# design.net
KiCad netlist of a schematic drawn in Altium Designer
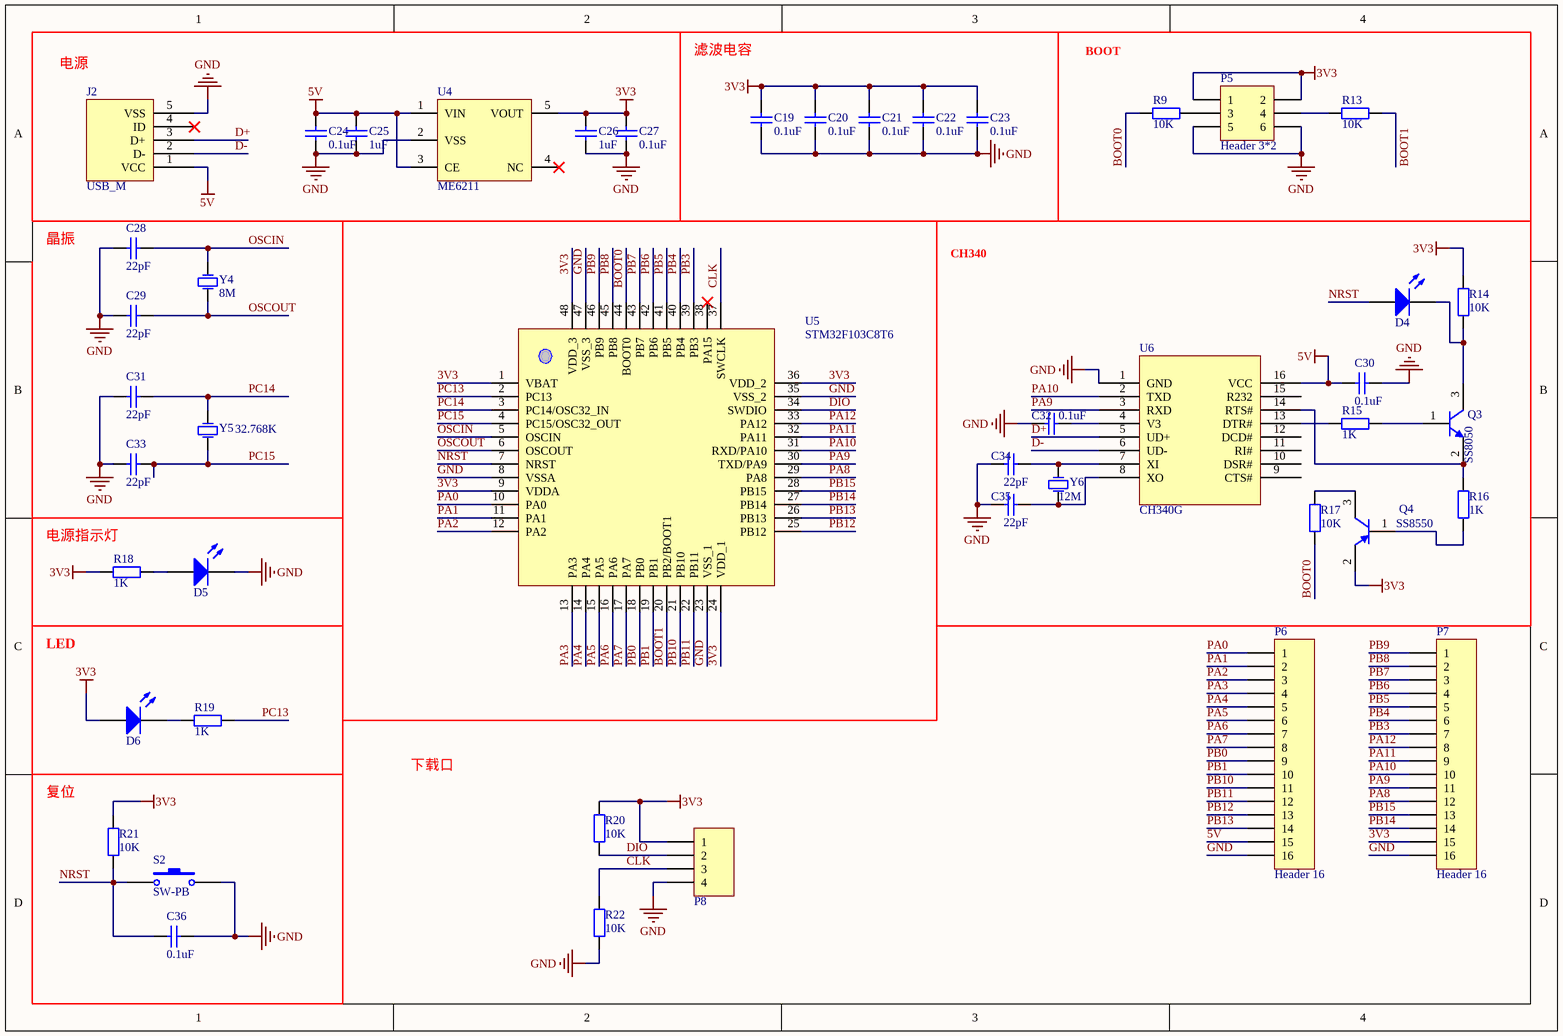
[diagram p0: 原理图.SchDoc]

(export (version "E")
  (design (tool "Eeschema 10.0.6"))
  (components
    (comp (ref "C19")
      (value "0.1uF")
      (footprint "0603_C")
      (description "无极性电容")
      (fields (field (name "Comment") "Cap") (field (name "PUBLISHER") "Altium Limited"))
      (libsource (lib "stm32test") (part "Cap"))
    )
    (comp (ref "C20")
      (value "0.1uF")
      (footprint "0603_C")
      (description "无极性电容")
      (fields (field (name "Comment") "Cap") (field (name "PUBLISHER") "Altium Limited"))
      (libsource (lib "stm32test") (part "Cap"))
    )
    (comp (ref "C21")
      (value "0.1uF")
      (footprint "0603_C")
      (description "无极性电容")
      (fields (field (name "Comment") "Cap") (field (name "PUBLISHER") "Altium Limited"))
      (libsource (lib "stm32test") (part "Cap"))
    )
    (comp (ref "C22")
      (value "0.1uF")
      (footprint "0603_C")
      (description "无极性电容")
      (fields (field (name "Comment") "Cap") (field (name "PUBLISHER") "Altium Limited"))
      (libsource (lib "stm32test") (part "Cap"))
    )
    (comp (ref "C23")
      (value "0.1uF")
      (footprint "0603_C")
      (description "无极性电容")
      (fields (field (name "Comment") "Cap") (field (name "PUBLISHER") "Altium Limited"))
      (libsource (lib "stm32test") (part "Cap"))
    )
    (comp (ref "C24")
      (value "0.1uF")
      (footprint "0603_C")
      (description "无极性电容")
      (fields (field (name "Comment") "Cap") (field (name "PUBLISHER") "Altium Limited"))
      (libsource (lib "stm32test") (part "Cap"))
    )
    (comp (ref "C25")
      (value "1uF")
      (footprint "0603_C")
      (description "无极性电容")
      (fields (field (name "Comment") "Cap") (field (name "PUBLISHER") "Altium Limited"))
      (libsource (lib "stm32test") (part "Cap"))
    )
    (comp (ref "C26")
      (value "1uF")
      (footprint "0603_C")
      (description "无极性电容")
      (fields (field (name "Comment") "Cap") (field (name "PUBLISHER") "Altium Limited"))
      (libsource (lib "stm32test") (part "Cap"))
    )
    (comp (ref "C27")
      (value "0.1uF")
      (footprint "0603_C")
      (description "无极性电容")
      (fields (field (name "Comment") "Cap") (field (name "PUBLISHER") "Altium Limited"))
      (libsource (lib "stm32test") (part "Cap"))
    )
    (comp (ref "C28")
      (value "22pF")
      (footprint "0603_C")
      (description "无极性电容")
      (fields (field (name "Comment") "Cap") (field (name "PUBLISHER") "Altium Limited"))
      (libsource (lib "stm32test") (part "Cap"))
    )
    (comp (ref "C29")
      (value "22pF")
      (footprint "0603_C")
      (description "无极性电容")
      (fields (field (name "Comment") "Cap") (field (name "PUBLISHER") "Altium Limited"))
      (libsource (lib "stm32test") (part "Cap"))
    )
    (comp (ref "C30")
      (value "0.1uF")
      (footprint "0603_C")
      (description "无极性电容")
      (fields (field (name "Comment") "Cap") (field (name "PUBLISHER") "Altium Limited"))
      (libsource (lib "stm32test") (part "Cap"))
    )
    (comp (ref "C31")
      (value "22pF")
      (footprint "0603_C")
      (description "无极性电容")
      (fields (field (name "Comment") "Cap") (field (name "PUBLISHER") "Altium Limited"))
      (libsource (lib "stm32test") (part "Cap"))
    )
    (comp (ref "C32")
      (value "0.1uF")
      (footprint "0603_C")
      (description "无极性电容")
      (fields (field (name "Comment") "Cap") (field (name "PUBLISHER") "Altium Limited"))
      (libsource (lib "stm32test") (part "Cap"))
    )
    (comp (ref "C33")
      (value "22pF")
      (footprint "0603_C")
      (description "无极性电容")
      (fields (field (name "Comment") "Cap") (field (name "PUBLISHER") "Altium Limited"))
      (libsource (lib "stm32test") (part "Cap"))
    )
    (comp (ref "C34")
      (value "22pF")
      (footprint "0603_C")
      (description "无极性电容")
      (fields (field (name "Comment") "Cap") (field (name "PUBLISHER") "Altium Limited"))
      (libsource (lib "stm32test") (part "Cap"))
    )
    (comp (ref "C35")
      (value "22pF")
      (footprint "0603_C")
      (description "无极性电容")
      (fields (field (name "Comment") "Cap") (field (name "PUBLISHER") "Altium Limited"))
      (libsource (lib "stm32test") (part "Cap"))
    )
    (comp (ref "C36")
      (value "0.1uF")
      (footprint "0603_C")
      (description "无极性电容")
      (fields (field (name "Comment") "Cap") (field (name "PUBLISHER") "Altium Limited"))
      (libsource (lib "stm32test") (part "Cap"))
    )
    (comp (ref "D4")
      (value "LED0")
      (footprint "LED_0805_Blue")
      (description "发光二极管")
      (fields (field (name "PUBLISHER") "Altium Limited"))
      (libsource (lib "stm32test") (part "LED0"))
    )
    (comp (ref "D5")
      (value "LED0")
      (footprint "LED_0805_Blue")
      (description "发光二极管")
      (fields (field (name "PUBLISHER") "Altium Limited"))
      (libsource (lib "stm32test") (part "LED0"))
    )
    (comp (ref "D6")
      (value "LED0")
      (footprint "LED_0805_Blue")
      (description "发光二极管")
      (fields (field (name "PUBLISHER") "Altium Limited"))
      (libsource (lib "stm32test") (part "LED0"))
    )
    (comp (ref "J2")
      (value "USB_M")
      (footprint "USB")
      (description "MicroUSB接口")
      (libsource (lib "stm32test") (part "USB_M"))
    )
    (comp (ref "P5")
      (value "Header 3*2")
      (footprint "HDR3X2")
      (description "接插件")
      (libsource (lib "stm32test") (part "Header 3*2"))
    )
    (comp (ref "P6")
      (value "Header 16")
      (footprint "HDR16X1_A")
      (description "Header16贴片")
      (fields (field (name "PUBLISHER") "Altium Limited"))
      (libsource (lib "stm32test") (part "Header 16"))
    )
    (comp (ref "P7")
      (value "Header 16")
      (footprint "HDR16X1_A")
      (description "Header16贴片")
      (fields (field (name "PUBLISHER") "Altium Limited"))
      (libsource (lib "stm32test") (part "Header 16"))
    )
    (comp (ref "P8")
      (value "Header 4")
      (footprint "HDR4X1_A")
      (description "接插件")
      (fields (field (name "PUBLISHER") "Altium Limited"))
      (libsource (lib "stm32test") (part "Header 4"))
    )
    (comp (ref "Q3")
      (value "SS8050")
      (footprint "SOT-23")
      (description "NPN贴片三极管")
      (fields (field (name "PUBLISHER") "Altium Limited"))
      (libsource (lib "stm32test") (part "SS8050"))
    )
    (comp (ref "Q4")
      (value "SS8550")
      (footprint "SOT-23")
      (description "PNP贴片三极管")
      (fields (field (name "PUBLISHER") "Altium Limited"))
      (libsource (lib "stm32test") (part "SS8550"))
    )
    (comp (ref "R9")
      (value "10K")
      (footprint "0603_R")
      (description "贴片电阻")
      (fields (field (name "Comment") "Res1") (field (name "PUBLISHER") "Altium Limited"))
      (libsource (lib "") (part "Res1_1"))
    )
    (comp (ref "R13")
      (value "10K")
      (footprint "0603_R")
      (description "贴片电阻")
      (fields (field (name "Comment") "Res1") (field (name "PUBLISHER") "Altium Limited"))
      (libsource (lib "") (part "Res1_1"))
    )
    (comp (ref "R14")
      (value "10K")
      (footprint "0603_R")
      (description "贴片电阻")
      (fields (field (name "Comment") "Res1") (field (name "PUBLISHER") "Altium Limited"))
      (libsource (lib "stm32test") (part "Res1"))
    )
    (comp (ref "R15")
      (value "1K")
      (footprint "0603_R")
      (description "贴片电阻")
      (fields (field (name "Comment") "Res1") (field (name "PUBLISHER") "Altium Limited"))
      (libsource (lib "") (part "Res1_1"))
    )
    (comp (ref "R16")
      (value "1K")
      (footprint "0603_R")
      (description "贴片电阻")
      (fields (field (name "Comment") "Res1") (field (name "PUBLISHER") "Altium Limited"))
      (libsource (lib "stm32test") (part "Res1"))
    )
    (comp (ref "R17")
      (value "10K")
      (footprint "0603_R")
      (description "贴片电阻")
      (fields (field (name "Comment") "Res1") (field (name "PUBLISHER") "Altium Limited"))
      (libsource (lib "stm32test") (part "Res1"))
    )
    (comp (ref "R18")
      (value "1K")
      (footprint "0603_R")
      (description "贴片电阻")
      (fields (field (name "Comment") "Res1") (field (name "PUBLISHER") "Altium Limited"))
      (libsource (lib "") (part "Res1_1"))
    )
    (comp (ref "R19")
      (value "1K")
      (footprint "0603_R")
      (description "贴片电阻")
      (fields (field (name "Comment") "Res1") (field (name "PUBLISHER") "Altium Limited"))
      (libsource (lib "") (part "Res1_1"))
    )
    (comp (ref "R20")
      (value "10K")
      (footprint "0603_R")
      (description "贴片电阻")
      (fields (field (name "Comment") "Res1") (field (name "PUBLISHER") "Altium Limited"))
      (libsource (lib "stm32test") (part "Res1"))
    )
    (comp (ref "R21")
      (value "10K")
      (footprint "0603_R")
      (description "贴片电阻")
      (fields (field (name "Comment") "Res1") (field (name "PUBLISHER") "Altium Limited"))
      (libsource (lib "stm32test") (part "Res1"))
    )
    (comp (ref "R22")
      (value "10K")
      (footprint "0603_R")
      (description "贴片电阻")
      (fields (field (name "Comment") "Res1") (field (name "PUBLISHER") "Altium Limited"))
      (libsource (lib "stm32test") (part "Res1"))
    )
    (comp (ref "S2")
      (value "SW-PB")
      (footprint "SW_PB2_A1")
      (description "微动开关")
      (fields (field (name "PUBLISHER") "Altium Limited"))
      (libsource (lib "stm32test") (part "SW-PB"))
    )
    (comp (ref "U4") (value "ME6211") (footprint "SOT23-5") (libsource (lib "stm32test") (part "ME6211")))
    (comp (ref "U5")
      (value "STM32F103C8T6")
      (footprint "LQFP-48_M")
      (description "STM32单片机48引脚")
      (libsource (lib "stm32test") (part "STM32F103C8T6"))
    )
    (comp (ref "U6")
      (value "CH340G")
      (footprint "SOP-16")
      (description "串口芯片")
      (libsource (lib "stm32test") (part "CH340G"))
    )
    (comp (ref "Y4")
      (value "8M")
      (footprint "5032")
      (description "晶振")
      (fields (field (name "PUBLISHER") "Altium Limited"))
      (libsource (lib "stm32test") (part "XTAL"))
    )
    (comp (ref "Y5")
      (value "32.768K")
      (footprint "3215")
      (description "晶振")
      (fields (field (name "PUBLISHER") "Altium Limited"))
      (libsource (lib "stm32test") (part "XTAL"))
    )
    (comp (ref "Y6")
      (value "12M")
      (footprint "5032")
      (description "晶振")
      (fields (field (name "PUBLISHER") "Altium Limited"))
      (libsource (lib "stm32test") (part "XTAL"))
    )
  )
  (nets
    (net (code "2") (name "/BOOT0") (class "Default")
      (node (ref "R17") (pin "1") (pinfunction "1_1") (pintype "passive"))
      (node (ref "R9") (pin "1") (pinfunction "1_1") (pintype "passive"))
      (node (ref "U5") (pin "44") (pinfunction "BOOT0_44") (pintype "passive"))
    )
    (net (code "3") (name "/BOOT1") (class "Default")
      (node (ref "R13") (pin "2") (pinfunction "2_2") (pintype "passive"))
      (node (ref "U5") (pin "20") (pinfunction "PB2/BOOT1_20") (pintype "passive"))
    )
    (net (code "4") (name "/CLK") (class "Default")
      (node (ref "P8") (pin "3") (pinfunction "3_3") (pintype "passive"))
      (node (ref "R22") (pin "2") (pinfunction "2_2") (pintype "passive"))
      (node (ref "U5") (pin "37") (pinfunction "SWCLK_37") (pintype "passive"))
    )
    (net (code "5") (name "/D+") (class "Default")
      (node (ref "J2") (pin "3") (pinfunction "D+_3") (pintype "passive"))
      (node (ref "U6") (pin "5") (pinfunction "UD+_5") (pintype "passive"))
    )
    (net (code "6") (name "/D-") (class "Default")
      (node (ref "J2") (pin "2") (pinfunction "D-_2") (pintype "passive"))
      (node (ref "U6") (pin "6") (pinfunction "UD-_6") (pintype "passive"))
    )
    (net (code "7") (name "/DIO") (class "Default")
      (node (ref "P8") (pin "2") (pinfunction "2_2") (pintype "passive"))
      (node (ref "R20") (pin "1") (pinfunction "1_1") (pintype "passive"))
      (node (ref "U5") (pin "34") (pinfunction "SWDIO_34") (pintype "passive"))
    )
    (net (code "8") (name "/NRST") (class "Default")
      (node (ref "C36") (pin "1") (pinfunction "1_1") (pintype "passive"))
      (node (ref "D4") (pin "1") (pinfunction "A_1") (pintype "passive"))
      (node (ref "R21") (pin "1") (pinfunction "1_1") (pintype "passive"))
      (node (ref "S2") (pin "1") (pinfunction "1_1") (pintype "passive"))
      (node (ref "U5") (pin "7") (pinfunction "NRST_7") (pintype "passive"))
    )
    (net (code "9") (name "/OSCIN") (class "Default")
      (node (ref "C28") (pin "1") (pinfunction "1_1") (pintype "passive"))
      (node (ref "U5") (pin "5") (pinfunction "OSCIN_5") (pintype "passive"))
      (node (ref "Y4") (pin "1") (pinfunction "OSC1_1") (pintype "passive"))
    )
    (net (code "10") (name "/OSCOUT") (class "Default")
      (node (ref "C29") (pin "1") (pinfunction "1_1") (pintype "passive"))
      (node (ref "U5") (pin "6") (pinfunction "OSCOUT_6") (pintype "passive"))
      (node (ref "Y4") (pin "2") (pinfunction "OSC2_2") (pintype "passive"))
    )
    (net (code "11") (name "/PA0") (class "Default")
      (node (ref "P6") (pin "1") (pinfunction "1_1") (pintype "passive"))
      (node (ref "U5") (pin "10") (pinfunction "PA0_10") (pintype "passive"))
    )
    (net (code "12") (name "/PA1") (class "Default")
      (node (ref "P6") (pin "2") (pinfunction "2_2") (pintype "passive"))
      (node (ref "U5") (pin "11") (pinfunction "PA1_11") (pintype "passive"))
    )
    (net (code "13") (name "/PA2") (class "Default")
      (node (ref "P6") (pin "3") (pinfunction "3_3") (pintype "passive"))
      (node (ref "U5") (pin "12") (pinfunction "PA2_12") (pintype "passive"))
    )
    (net (code "14") (name "/PA3") (class "Default")
      (node (ref "P6") (pin "4") (pinfunction "4_4") (pintype "passive"))
      (node (ref "U5") (pin "13") (pinfunction "PA3_13") (pintype "passive"))
    )
    (net (code "15") (name "/PA4") (class "Default")
      (node (ref "P6") (pin "5") (pinfunction "5_5") (pintype "passive"))
      (node (ref "U5") (pin "14") (pinfunction "PA4_14") (pintype "passive"))
    )
    (net (code "16") (name "/PA5") (class "Default")
      (node (ref "P6") (pin "6") (pinfunction "6_6") (pintype "passive"))
      (node (ref "U5") (pin "15") (pinfunction "PA5_15") (pintype "passive"))
    )
    (net (code "17") (name "/PA6") (class "Default")
      (node (ref "P6") (pin "7") (pinfunction "7_7") (pintype "passive"))
      (node (ref "U5") (pin "16") (pinfunction "PA6_16") (pintype "passive"))
    )
    (net (code "18") (name "/PA7") (class "Default")
      (node (ref "P6") (pin "8") (pinfunction "8_8") (pintype "passive"))
      (node (ref "U5") (pin "17") (pinfunction "PA7_17") (pintype "passive"))
    )
    (net (code "19") (name "/PA8") (class "Default")
      (node (ref "P7") (pin "12") (pinfunction "12_12") (pintype "passive"))
      (node (ref "U5") (pin "29") (pinfunction "PA8_29") (pintype "passive"))
    )
    (net (code "20") (name "/PA9") (class "Default")
      (node (ref "P7") (pin "11") (pinfunction "11_11") (pintype "passive"))
      (node (ref "U5") (pin "30") (pinfunction "TXD/PA9_30") (pintype "passive"))
      (node (ref "U6") (pin "3") (pinfunction "RXD_3") (pintype "passive"))
    )
    (net (code "21") (name "/PA10") (class "Default")
      (node (ref "P7") (pin "10") (pinfunction "10_10") (pintype "passive"))
      (node (ref "U5") (pin "31") (pinfunction "RXD/PA10_31") (pintype "passive"))
      (node (ref "U6") (pin "2") (pinfunction "TXD_2") (pintype "passive"))
    )
    (net (code "22") (name "/PA11") (class "Default")
      (node (ref "P7") (pin "9") (pinfunction "9_9") (pintype "passive"))
      (node (ref "U5") (pin "32") (pinfunction "PA11_32") (pintype "passive"))
    )
    (net (code "23") (name "/PA12") (class "Default")
      (node (ref "P7") (pin "8") (pinfunction "8_8") (pintype "passive"))
      (node (ref "U5") (pin "33") (pinfunction "PA12_33") (pintype "passive"))
    )
    (net (code "24") (name "/PB0") (class "Default")
      (node (ref "P6") (pin "9") (pinfunction "9_9") (pintype "passive"))
      (node (ref "U5") (pin "18") (pinfunction "PB0_18") (pintype "passive"))
    )
    (net (code "25") (name "/PB1") (class "Default")
      (node (ref "P6") (pin "10") (pinfunction "10_10") (pintype "passive"))
      (node (ref "U5") (pin "19") (pinfunction "PB1_19") (pintype "passive"))
    )
    (net (code "26") (name "/PB3") (class "Default")
      (node (ref "P7") (pin "7") (pinfunction "7_7") (pintype "passive"))
      (node (ref "U5") (pin "39") (pinfunction "PB3_39") (pintype "passive"))
    )
    (net (code "27") (name "/PB4") (class "Default")
      (node (ref "P7") (pin "6") (pinfunction "6_6") (pintype "passive"))
      (node (ref "U5") (pin "40") (pinfunction "PB4_40") (pintype "passive"))
    )
    (net (code "28") (name "/PB5") (class "Default")
      (node (ref "P7") (pin "5") (pinfunction "5_5") (pintype "passive"))
      (node (ref "U5") (pin "41") (pinfunction "PB5_41") (pintype "passive"))
    )
    (net (code "29") (name "/PB6") (class "Default")
      (node (ref "P7") (pin "4") (pinfunction "4_4") (pintype "passive"))
      (node (ref "U5") (pin "42") (pinfunction "PB6_42") (pintype "passive"))
    )
    (net (code "30") (name "/PB7") (class "Default")
      (node (ref "P7") (pin "3") (pinfunction "3_3") (pintype "passive"))
      (node (ref "U5") (pin "43") (pinfunction "PB7_43") (pintype "passive"))
    )
    (net (code "31") (name "/PB8") (class "Default")
      (node (ref "P7") (pin "2") (pinfunction "2_2") (pintype "passive"))
      (node (ref "U5") (pin "45") (pinfunction "PB8_45") (pintype "passive"))
    )
    (net (code "32") (name "/PB9") (class "Default")
      (node (ref "P7") (pin "1") (pinfunction "1_1") (pintype "passive"))
      (node (ref "U5") (pin "46") (pinfunction "PB9_46") (pintype "passive"))
    )
    (net (code "33") (name "/PB10") (class "Default")
      (node (ref "P6") (pin "11") (pinfunction "11_11") (pintype "passive"))
      (node (ref "U5") (pin "21") (pinfunction "PB10_21") (pintype "passive"))
    )
    (net (code "34") (name "/PB11") (class "Default")
      (node (ref "P6") (pin "12") (pinfunction "12_12") (pintype "passive"))
      (node (ref "U5") (pin "22") (pinfunction "PB11_22") (pintype "passive"))
    )
    (net (code "35") (name "/PB12") (class "Default")
      (node (ref "P6") (pin "13") (pinfunction "13_13") (pintype "passive"))
      (node (ref "U5") (pin "25") (pinfunction "PB12_25") (pintype "passive"))
    )
    (net (code "36") (name "/PB13") (class "Default")
      (node (ref "P6") (pin "14") (pinfunction "14_14") (pintype "passive"))
      (node (ref "U5") (pin "26") (pinfunction "PB13_26") (pintype "passive"))
    )
    (net (code "37") (name "/PB14") (class "Default")
      (node (ref "P7") (pin "14") (pinfunction "14_14") (pintype "passive"))
      (node (ref "U5") (pin "27") (pinfunction "PB14_27") (pintype "passive"))
    )
    (net (code "38") (name "/PB15") (class "Default")
      (node (ref "P7") (pin "13") (pinfunction "13_13") (pintype "passive"))
      (node (ref "U5") (pin "28") (pinfunction "PB15_28") (pintype "passive"))
    )
    (net (code "39") (name "/PC13") (class "Default")
      (node (ref "R19") (pin "2") (pinfunction "2_2") (pintype "passive"))
      (node (ref "U5") (pin "2") (pinfunction "PC13_2") (pintype "passive"))
    )
    (net (code "40") (name "/PC14") (class "Default")
      (node (ref "C31") (pin "1") (pinfunction "1_1") (pintype "passive"))
      (node (ref "U5") (pin "3") (pinfunction "PC14/OSC32_IN_3") (pintype "passive"))
      (node (ref "Y5") (pin "1") (pinfunction "OSC1_1") (pintype "passive"))
    )
    (net (code "41") (name "/PC15") (class "Default")
      (node (ref "C33") (pin "1") (pinfunction "1_1") (pintype "passive"))
      (node (ref "U5") (pin "4") (pinfunction "PC15/OSC32_OUT_4") (pintype "passive"))
      (node (ref "Y5") (pin "2") (pinfunction "OSC2_2") (pintype "passive"))
    )
    (net (code "42") (name "3V3") (class "Default")
      (node (ref "C19") (pin "2") (pinfunction "2_2") (pintype "passive"))
      (node (ref "C20") (pin "2") (pinfunction "2_2") (pintype "passive"))
      (node (ref "C21") (pin "2") (pinfunction "2_2") (pintype "passive"))
      (node (ref "C22") (pin "2") (pinfunction "2_2") (pintype "passive"))
      (node (ref "C23") (pin "2") (pinfunction "2_2") (pintype "passive"))
      (node (ref "C26") (pin "2") (pinfunction "2_2") (pintype "passive"))
      (node (ref "C27") (pin "2") (pinfunction "2_2") (pintype "passive"))
      (node (ref "D6") (pin "1") (pinfunction "A_1") (pintype "passive"))
      (node (ref "P5") (pin "1") (pinfunction "1_1") (pintype "passive"))
      (node (ref "P5") (pin "2") (pinfunction "2_2") (pintype "passive"))
      (node (ref "P7") (pin "15") (pinfunction "15_15") (pintype "passive"))
      (node (ref "P8") (pin "1") (pinfunction "1_1") (pintype "passive"))
      (node (ref "Q4") (pin "2") (pinfunction "E_2") (pintype "passive"))
      (node (ref "R14") (pin "2") (pinfunction "2_2") (pintype "passive"))
      (node (ref "R18") (pin "1") (pinfunction "1_1") (pintype "passive"))
      (node (ref "R20") (pin "2") (pinfunction "2_2") (pintype "passive"))
      (node (ref "R21") (pin "2") (pinfunction "2_2") (pintype "passive"))
      (node (ref "U4") (pin "5") (pinfunction "VOUT_5") (pintype "passive"))
      (node (ref "U5") (pin "1") (pinfunction "VBAT_1") (pintype "passive"))
      (node (ref "U5") (pin "24") (pinfunction "VDD_1_24") (pintype "passive"))
      (node (ref "U5") (pin "36") (pinfunction "VDD_2_36") (pintype "passive"))
      (node (ref "U5") (pin "48") (pinfunction "VDD_3_48") (pintype "passive"))
      (node (ref "U5") (pin "9") (pinfunction "VDDA_9") (pintype "passive"))
    )
    (net (code "43") (name "5V") (class "Default")
      (node (ref "C24") (pin "2") (pinfunction "2_2") (pintype "passive"))
      (node (ref "C25") (pin "2") (pinfunction "2_2") (pintype "passive"))
      (node (ref "C30") (pin "1") (pinfunction "1_1") (pintype "passive"))
      (node (ref "J2") (pin "1") (pinfunction "VCC_1") (pintype "passive"))
      (node (ref "P6") (pin "15") (pinfunction "15_15") (pintype "passive"))
      (node (ref "U4") (pin "1") (pinfunction "VIN_1") (pintype "passive"))
      (node (ref "U4") (pin "3") (pinfunction "CE_3") (pintype "passive"))
      (node (ref "U6") (pin "16") (pinfunction "VCC_16") (pintype "power_in"))
    )
    (net (code "44") (name "GND") (class "Default")
      (node (ref "C19") (pin "1") (pinfunction "1_1") (pintype "passive"))
      (node (ref "C20") (pin "1") (pinfunction "1_1") (pintype "passive"))
      (node (ref "C21") (pin "1") (pinfunction "1_1") (pintype "passive"))
      (node (ref "C22") (pin "1") (pinfunction "1_1") (pintype "passive"))
      (node (ref "C23") (pin "1") (pinfunction "1_1") (pintype "passive"))
      (node (ref "C24") (pin "1") (pinfunction "1_1") (pintype "passive"))
      (node (ref "C25") (pin "1") (pinfunction "1_1") (pintype "passive"))
      (node (ref "C26") (pin "1") (pinfunction "1_1") (pintype "passive"))
      (node (ref "C27") (pin "1") (pinfunction "1_1") (pintype "passive"))
      (node (ref "C28") (pin "2") (pinfunction "2_2") (pintype "passive"))
      (node (ref "C29") (pin "2") (pinfunction "2_2") (pintype "passive"))
      (node (ref "C30") (pin "2") (pinfunction "2_2") (pintype "passive"))
      (node (ref "C31") (pin "2") (pinfunction "2_2") (pintype "passive"))
      (node (ref "C32") (pin "1") (pinfunction "1_1") (pintype "passive"))
      (node (ref "C33") (pin "2") (pinfunction "2_2") (pintype "passive"))
      (node (ref "C34") (pin "2") (pinfunction "2_2") (pintype "passive"))
      (node (ref "C35") (pin "2") (pinfunction "2_2") (pintype "passive"))
      (node (ref "C36") (pin "2") (pinfunction "2_2") (pintype "passive"))
      (node (ref "D5") (pin "2") (pinfunction "K_2") (pintype "passive"))
      (node (ref "J2") (pin "5") (pinfunction "VSS_5") (pintype "passive"))
      (node (ref "P5") (pin "5") (pinfunction "5_5") (pintype "passive"))
      (node (ref "P5") (pin "6") (pinfunction "6_6") (pintype "passive"))
      (node (ref "P6") (pin "16") (pinfunction "16_16") (pintype "passive"))
      (node (ref "P7") (pin "16") (pinfunction "16_16") (pintype "passive"))
      (node (ref "P8") (pin "4") (pinfunction "4_4") (pintype "passive"))
      (node (ref "R22") (pin "1") (pinfunction "1_1") (pintype "passive"))
      (node (ref "S2") (pin "2") (pinfunction "2_2") (pintype "passive"))
      (node (ref "U4") (pin "2") (pinfunction "VSS_2") (pintype "passive"))
      (node (ref "U5") (pin "23") (pinfunction "VSS_1_23") (pintype "passive"))
      (node (ref "U5") (pin "35") (pinfunction "VSS_2_35") (pintype "passive"))
      (node (ref "U5") (pin "47") (pinfunction "VSS_3_47") (pintype "passive"))
      (node (ref "U5") (pin "8") (pinfunction "VSSA_8") (pintype "passive"))
      (node (ref "U6") (pin "1") (pinfunction "GND_1") (pintype "power_in"))
    )
    (net (code "45") (name "Net-(D4-K)") (class "Default")
      (node (ref "D4") (pin "2") (pinfunction "K_2") (pintype "passive"))
      (node (ref "Q3") (pin "3") (pinfunction "C_3") (pintype "passive"))
      (node (ref "R14") (pin "1") (pinfunction "1_1") (pintype "passive"))
    )
    (net (code "46") (name "Net-(D5-A)") (class "Default")
      (node (ref "D5") (pin "1") (pinfunction "A_1") (pintype "passive"))
      (node (ref "R18") (pin "2") (pinfunction "2_2") (pintype "passive"))
    )
    (net (code "47") (name "Net-(D6-K)") (class "Default")
      (node (ref "D6") (pin "2") (pinfunction "K_2") (pintype "passive"))
      (node (ref "R19") (pin "1") (pinfunction "1_1") (pintype "passive"))
    )
    (net (code "48") (name "Net-(P5-Pad3)") (class "Default")
      (node (ref "P5") (pin "3") (pinfunction "3_3") (pintype "passive"))
      (node (ref "R9") (pin "2") (pinfunction "2_2") (pintype "passive"))
    )
    (net (code "49") (name "Net-(P5-Pad4)") (class "Default")
      (node (ref "P5") (pin "4") (pinfunction "4_4") (pintype "passive"))
      (node (ref "R13") (pin "1") (pinfunction "1_1") (pintype "passive"))
    )
    (net (code "50") (name "Net-(Q3-B)") (class "Default")
      (node (ref "Q3") (pin "1") (pinfunction "B_1") (pintype "passive"))
      (node (ref "R15") (pin "2") (pinfunction "2_2") (pintype "passive"))
    )
    (net (code "51") (name "Net-(Q3-E)") (class "Default")
      (node (ref "Q3") (pin "2") (pinfunction "E_2") (pintype "passive"))
      (node (ref "R16") (pin "2") (pinfunction "2_2") (pintype "passive"))
      (node (ref "U6") (pin "14") (pinfunction "RTS#_14") (pintype "passive"))
    )
    (net (code "52") (name "Net-(Q4-B)") (class "Default")
      (node (ref "Q4") (pin "1") (pinfunction "B_1") (pintype "passive"))
      (node (ref "R16") (pin "1") (pinfunction "1_1") (pintype "passive"))
    )
    (net (code "53") (name "Net-(Q4-C)") (class "Default")
      (node (ref "Q4") (pin "3") (pinfunction "C_3") (pintype "passive"))
      (node (ref "R17") (pin "2") (pinfunction "2_2") (pintype "passive"))
    )
    (net (code "54") (name "Net-(U6-DTR#)") (class "Default")
      (node (ref "R15") (pin "1") (pinfunction "1_1") (pintype "passive"))
      (node (ref "U6") (pin "13") (pinfunction "DTR#_13") (pintype "passive"))
    )
    (net (code "55") (name "Net-(U6-V3)") (class "Default")
      (node (ref "C32") (pin "2") (pinfunction "2_2") (pintype "passive"))
      (node (ref "U6") (pin "4") (pinfunction "V3_4") (pintype "power_in"))
    )
    (net (code "56") (name "Net-(U6-XI)") (class "Default")
      (node (ref "C34") (pin "1") (pinfunction "1_1") (pintype "passive"))
      (node (ref "U6") (pin "7") (pinfunction "XI_7") (pintype "passive"))
      (node (ref "Y6") (pin "1") (pinfunction "OSC1_1") (pintype "passive"))
    )
    (net (code "57") (name "Net-(U6-XO)") (class "Default")
      (node (ref "C35") (pin "1") (pinfunction "1_1") (pintype "passive"))
      (node (ref "U6") (pin "8") (pinfunction "XO_8") (pintype "passive"))
      (node (ref "Y6") (pin "2") (pinfunction "OSC2_2") (pintype "passive"))
    )
    (net (code "58") (name "unconnected-(J2-ID-Pad4)") (class "Default")
      (node (ref "J2") (pin "4") (pinfunction "ID_4") (pintype "passive+no_connect"))
    )
    (net (code "59") (name "unconnected-(U4-NC-Pad4)") (class "Default")
      (node (ref "U4") (pin "4") (pinfunction "NC_4") (pintype "passive+no_connect"))
    )
    (net (code "60") (name "unconnected-(U5-PA15-Pad38)") (class "Default")
      (node (ref "U5") (pin "38") (pinfunction "PA15_38") (pintype "passive+no_connect"))
    )
    (net (code "61") (name "unconnected-(U6-CTS#-Pad9)") (class "Default")
      (node (ref "U6") (pin "9") (pinfunction "CTS#_9") (pintype "passive"))
    )
    (net (code "62") (name "unconnected-(U6-DCD#-Pad12)") (class "Default")
      (node (ref "U6") (pin "12") (pinfunction "DCD#_12") (pintype "passive"))
    )
    (net (code "63") (name "unconnected-(U6-DSR#-Pad10)") (class "Default")
      (node (ref "U6") (pin "10") (pinfunction "DSR#_10") (pintype "passive"))
    )
    (net (code "64") (name "unconnected-(U6-R232-Pad15)") (class "Default")
      (node (ref "U6") (pin "15") (pinfunction "R232_15") (pintype "passive"))
    )
    (net (code "65") (name "unconnected-(U6-RI#-Pad11)") (class "Default")
      (node (ref "U6") (pin "11") (pinfunction "RI#_11") (pintype "passive"))
    )
  )
)
